# Trail__Con.net
KiCad netlist of a schematic drawn in EAGLE
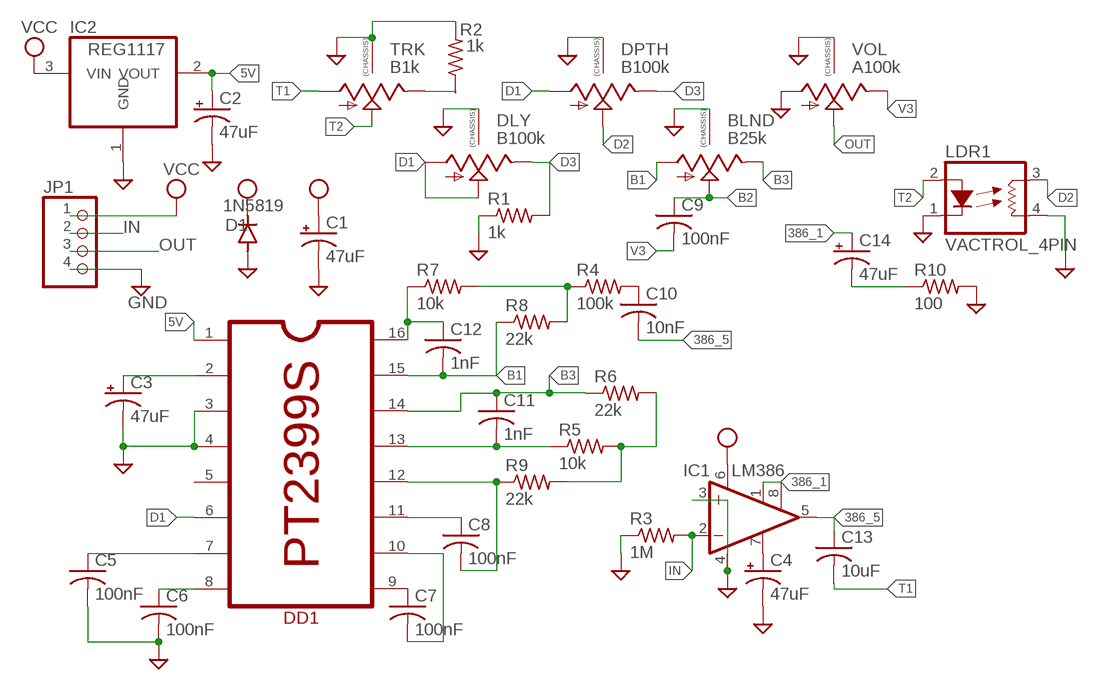
[diagram p0: schematic, sheet 1]

(export (version "E")
  (design (tool "Eeschema 10.0.6"))
  (components
    (comp (ref "BLND")
      (value "B25k")
      (footprint "eagle-import:9MM_SNAP-IN_POT")
      (libsource (lib "eagle-import") (part "9MM_SNAP-IN_POT_CHASSIS"))
    )
    (comp (ref "C1")
      (value "47uF")
      (footprint "eagle-import:PAN_B_SMD+THRU")
      (libsource (lib "eagle-import") (part "CAP_SMD+THRUPAN_B"))
    )
    (comp (ref "C2")
      (value "47uF")
      (footprint "eagle-import:PAN_B_SMD+THRU")
      (libsource (lib "eagle-import") (part "CAP_SMD+THRUPAN_B"))
    )
    (comp (ref "C3")
      (value "47uF")
      (footprint "eagle-import:PAN_B_SMD+THRU")
      (libsource (lib "eagle-import") (part "CAP_SMD+THRUPAN_B"))
    )
    (comp (ref "C4")
      (value "47uF")
      (footprint "eagle-import:PAN_B_SMD+THRU")
      (libsource (lib "eagle-import") (part "CAP_SMD+THRUPAN_B"))
    )
    (comp (ref "C5")
      (value "100nF")
      (footprint "eagle-import:C0402")
      (libsource (lib "eagle-import") (part "C-USC0402"))
    )
    (comp (ref "C6")
      (value "100nF")
      (footprint "eagle-import:C0402")
      (libsource (lib "eagle-import") (part "C-USC0402"))
    )
    (comp (ref "C7")
      (value "100nF")
      (footprint "eagle-import:C0402")
      (libsource (lib "eagle-import") (part "C-USC0402"))
    )
    (comp (ref "C8")
      (value "100nF")
      (footprint "eagle-import:C0402")
      (libsource (lib "eagle-import") (part "C-USC0402"))
    )
    (comp (ref "C9")
      (value "100nF")
      (footprint "eagle-import:C0402")
      (libsource (lib "eagle-import") (part "C-USC0402"))
    )
    (comp (ref "C10")
      (value "10nF")
      (footprint "eagle-import:C0402")
      (libsource (lib "eagle-import") (part "C-USC0402"))
    )
    (comp (ref "C11")
      (value "1nF")
      (footprint "eagle-import:C0402")
      (libsource (lib "eagle-import") (part "C-USC0402"))
    )
    (comp (ref "C12")
      (value "1nF")
      (footprint "eagle-import:C0402")
      (libsource (lib "eagle-import") (part "C-USC0402"))
    )
    (comp (ref "C13")
      (value "10uF")
      (footprint "eagle-import:C0805")
      (libsource (lib "eagle-import") (part "C-USC0805"))
    )
    (comp (ref "C14")
      (value "47uF")
      (footprint "eagle-import:PAN_B_SMD+THRU")
      (libsource (lib "eagle-import") (part "CAP_SMD+THRUPAN_B"))
    )
    (comp (ref "D1")
      (value "1N5819")
      (footprint "eagle-import:SOD123")
      (libsource (lib "eagle-import") (part "DIODE-SOD123"))
    )
    (comp (ref "DD1")
      (value "PT2399S")
      (footprint "eagle-import:SO-16")
      (libsource (lib "eagle-import") (part "PT2399S"))
    )
    (comp (ref "DLY")
      (value "B100k")
      (footprint "eagle-import:9MM_SNAP-IN_POT")
      (libsource (lib "eagle-import") (part "9MM_SNAP-IN_POT_CHASSIS"))
    )
    (comp (ref "DPTH")
      (value "B100k")
      (footprint "eagle-import:9MM_SNAP-IN_POT")
      (libsource (lib "eagle-import") (part "9MM_SNAP-IN_POT_CHASSIS"))
    )
    (comp (ref "IC1")
      (value "LM386")
      (footprint "eagle-import:SO08")
      (libsource (lib "eagle-import") (part "LM386?-M1"))
    )
    (comp (ref "IC2")
      (value "REG1117")
      (footprint "eagle-import:SOT223")
      (libsource (lib "eagle-import") (part "REG1117"))
    )
    (comp (ref "JP1")
      (value "PINHD-1X4")
      (footprint "eagle-import:1X04")
      (libsource (lib "eagle-import") (part "PINHD-1X4"))
    )
    (comp (ref "LDR1")
      (value "VACTROL_4PIN")
      (footprint "eagle-import:VACTROL_4PIN_VTL5C")
      (libsource (lib "eagle-import") (part "VACTROL_4PIN"))
    )
    (comp (ref "R1")
      (value "1k")
      (footprint "eagle-import:R0402")
      (libsource (lib "eagle-import") (part "R-US_R0402"))
    )
    (comp (ref "R2")
      (value "1k")
      (footprint "eagle-import:R0402")
      (libsource (lib "eagle-import") (part "R-US_R0402"))
    )
    (comp (ref "R3")
      (value "1M")
      (footprint "eagle-import:R0402")
      (libsource (lib "eagle-import") (part "R-US_R0402"))
    )
    (comp (ref "R4")
      (value "100k")
      (footprint "eagle-import:R0402")
      (libsource (lib "eagle-import") (part "R-US_R0402"))
    )
    (comp (ref "R5")
      (value "10k")
      (footprint "eagle-import:R0402")
      (libsource (lib "eagle-import") (part "R-US_R0402"))
    )
    (comp (ref "R6")
      (value "22k")
      (footprint "eagle-import:R0402")
      (libsource (lib "eagle-import") (part "R-US_R0402"))
    )
    (comp (ref "R7")
      (value "10k")
      (footprint "eagle-import:R0402")
      (libsource (lib "eagle-import") (part "R-US_R0402"))
    )
    (comp (ref "R8")
      (value "22k")
      (footprint "eagle-import:R0402")
      (libsource (lib "eagle-import") (part "R-US_R0402"))
    )
    (comp (ref "R9")
      (value "22k")
      (footprint "eagle-import:R0402")
      (libsource (lib "eagle-import") (part "R-US_R0402"))
    )
    (comp (ref "R10")
      (value "100")
      (footprint "eagle-import:R0402")
      (libsource (lib "eagle-import") (part "R-US_R0402"))
    )
    (comp (ref "TRK")
      (value "B1k")
      (footprint "eagle-import:9MM_SNAP-IN_POT")
      (libsource (lib "eagle-import") (part "9MM_SNAP-IN_POT_CHASSIS"))
    )
    (comp (ref "VOL")
      (value "A100k")
      (footprint "eagle-import:9MM_SNAP-IN_POT")
      (libsource (lib "eagle-import") (part "9MM_SNAP-IN_POT_CHASSIS"))
    )
  )
  (nets
    (net (code "1") (name "5V") (class "Default")
      (node (ref "C2") (pin "+") (pinfunction "+_+") (pintype "passive"))
      (node (ref "C2") (pin "++") (pinfunction "+_++") (pintype "passive"))
      (node (ref "DD1") (pin "1") (pinfunction "1_1") (pintype "bidirectional"))
      (node (ref "IC2") (pin "2") (pinfunction "VOUT_2") (pintype "output"))
    )
    (net (code "2") (name "386_1") (class "Default")
      (node (ref "C14") (pin "+") (pinfunction "+_+") (pintype "passive"))
      (node (ref "C14") (pin "++") (pinfunction "+_++") (pintype "passive"))
      (node (ref "IC1") (pin "1") (pinfunction "GAIN_1") (pintype "passive"))
      (node (ref "IC1") (pin "8") (pinfunction "GAIN_8") (pintype "passive"))
    )
    (net (code "3") (name "386_5") (class "Default")
      (node (ref "C10") (pin "2") (pinfunction "2_2") (pintype "passive"))
      (node (ref "C13") (pin "1") (pinfunction "1_1") (pintype "passive"))
      (node (ref "IC1") (pin "5") (pinfunction "OUT_5") (pintype "output"))
    )
    (net (code "4") (name "B1") (class "Default")
      (node (ref "BLND") (pin "1") (pinfunction "A_1") (pintype "passive"))
      (node (ref "C12") (pin "2") (pinfunction "2_2") (pintype "passive"))
      (node (ref "DD1") (pin "15") (pinfunction "15_15") (pintype "bidirectional"))
      (node (ref "R8") (pin "1") (pinfunction "1_1") (pintype "passive"))
    )
    (net (code "5") (name "B2") (class "Default")
      (node (ref "BLND") (pin "2") (pinfunction "S_2") (pintype "passive"))
      (node (ref "C9") (pin "1") (pinfunction "1_1") (pintype "passive"))
    )
    (net (code "6") (name "B3") (class "Default")
      (node (ref "BLND") (pin "3") (pinfunction "E_3") (pintype "passive"))
      (node (ref "C11") (pin "1") (pinfunction "1_1") (pintype "passive"))
      (node (ref "DD1") (pin "14") (pinfunction "14_14") (pintype "bidirectional"))
      (node (ref "R6") (pin "1") (pinfunction "1_1") (pintype "passive"))
    )
    (net (code "7") (name "D1") (class "Default")
      (node (ref "DD1") (pin "6") (pinfunction "6_6") (pintype "bidirectional"))
      (node (ref "DLY") (pin "1") (pinfunction "A_1") (pintype "passive"))
      (node (ref "DLY") (pin "2") (pinfunction "S_2") (pintype "passive"))
      (node (ref "DPTH") (pin "1") (pinfunction "A_1") (pintype "passive"))
    )
    (net (code "8") (name "D2") (class "Default")
      (node (ref "DPTH") (pin "2") (pinfunction "S_2") (pintype "passive"))
      (node (ref "LDR1") (pin "3") (pinfunction "RES1_3") (pintype "passive"))
    )
    (net (code "9") (name "D3") (class "Default")
      (node (ref "DLY") (pin "3") (pinfunction "E_3") (pintype "passive"))
      (node (ref "DPTH") (pin "3") (pinfunction "E_3") (pintype "passive"))
      (node (ref "R1") (pin "2") (pinfunction "2_2") (pintype "passive"))
    )
    (net (code "10") (name "GND") (class "Default")
      (node (ref "BLND") (pin "CHASSIS1") (pinfunction "P$1_CHASSIS1") (pintype "passive"))
      (node (ref "BLND") (pin "CHASSIS2") (pinfunction "P$1_CHASSIS2") (pintype "passive"))
      (node (ref "C1") (pin "-") (pinfunction "-_-") (pintype "passive"))
      (node (ref "C1") (pin "--") (pinfunction "-_--") (pintype "passive"))
      (node (ref "C2") (pin "-") (pinfunction "-_-") (pintype "passive"))
      (node (ref "C2") (pin "--") (pinfunction "-_--") (pintype "passive"))
      (node (ref "C3") (pin "-") (pinfunction "-_-") (pintype "passive"))
      (node (ref "C3") (pin "--") (pinfunction "-_--") (pintype "passive"))
      (node (ref "C4") (pin "-") (pinfunction "-_-") (pintype "passive"))
      (node (ref "C4") (pin "--") (pinfunction "-_--") (pintype "passive"))
      (node (ref "C5") (pin "2") (pinfunction "2_2") (pintype "passive"))
      (node (ref "C6") (pin "2") (pinfunction "2_2") (pintype "passive"))
      (node (ref "D1") (pin "A") (pinfunction "A_A") (pintype "passive"))
      (node (ref "DD1") (pin "3") (pinfunction "3_3") (pintype "bidirectional"))
      (node (ref "DD1") (pin "4") (pinfunction "4_4") (pintype "bidirectional"))
      (node (ref "DLY") (pin "CHASSIS1") (pinfunction "P$1_CHASSIS1") (pintype "passive"))
      (node (ref "DLY") (pin "CHASSIS2") (pinfunction "P$1_CHASSIS2") (pintype "passive"))
      (node (ref "DPTH") (pin "CHASSIS1") (pinfunction "P$1_CHASSIS1") (pintype "passive"))
      (node (ref "DPTH") (pin "CHASSIS2") (pinfunction "P$1_CHASSIS2") (pintype "passive"))
      (node (ref "IC1") (pin "3") (pinfunction "+IN_3") (pintype "input"))
      (node (ref "IC1") (pin "4") (pinfunction "GND_4") (pintype "power_in"))
      (node (ref "IC2") (pin "1") (pinfunction "GND_1") (pintype "power_in"))
      (node (ref "JP1") (pin "4") (pinfunction "4_4") (pintype "passive"))
      (node (ref "LDR1") (pin "1") (pinfunction "LED-_1") (pintype "passive"))
      (node (ref "LDR1") (pin "4") (pinfunction "RES2_4") (pintype "passive"))
      (node (ref "R1") (pin "1") (pinfunction "1_1") (pintype "passive"))
      (node (ref "R10") (pin "2") (pinfunction "2_2") (pintype "passive"))
      (node (ref "R2") (pin "2") (pinfunction "2_2") (pintype "passive"))
      (node (ref "R3") (pin "1") (pinfunction "1_1") (pintype "passive"))
      (node (ref "TRK") (pin "CHASSIS1") (pinfunction "P$1_CHASSIS1") (pintype "passive"))
      (node (ref "TRK") (pin "CHASSIS2") (pinfunction "P$1_CHASSIS2") (pintype "passive"))
      (node (ref "VOL") (pin "1") (pinfunction "A_1") (pintype "passive"))
      (node (ref "VOL") (pin "CHASSIS1") (pinfunction "P$1_CHASSIS1") (pintype "passive"))
      (node (ref "VOL") (pin "CHASSIS2") (pinfunction "P$1_CHASSIS2") (pintype "passive"))
    )
    (net (code "11") (name "IN") (class "Default")
      (node (ref "IC1") (pin "2") (pinfunction "-IN_2") (pintype "input"))
      (node (ref "JP1") (pin "2") (pinfunction "2_2") (pintype "passive"))
      (node (ref "R3") (pin "2") (pinfunction "2_2") (pintype "passive"))
    )
    (net (code "12") (name "Net-(C3-+-Pad++)") (class "Default")
      (node (ref "C3") (pin "+") (pinfunction "+_+") (pintype "passive"))
      (node (ref "C3") (pin "++") (pinfunction "+_++") (pintype "passive"))
      (node (ref "DD1") (pin "2") (pinfunction "2_2") (pintype "bidirectional"))
    )
    (net (code "13") (name "Net-(C5-Pad1)") (class "Default")
      (node (ref "C5") (pin "1") (pinfunction "1_1") (pintype "passive"))
      (node (ref "DD1") (pin "7") (pinfunction "7_7") (pintype "bidirectional"))
    )
    (net (code "14") (name "Net-(C6-Pad1)") (class "Default")
      (node (ref "C6") (pin "1") (pinfunction "1_1") (pintype "passive"))
      (node (ref "DD1") (pin "8") (pinfunction "8_8") (pintype "bidirectional"))
    )
    (net (code "15") (name "Net-(C7-Pad1)") (class "Default")
      (node (ref "C7") (pin "1") (pinfunction "1_1") (pintype "passive"))
      (node (ref "DD1") (pin "9") (pinfunction "9_9") (pintype "bidirectional"))
    )
    (net (code "16") (name "Net-(C7-Pad2)") (class "Default")
      (node (ref "C7") (pin "2") (pinfunction "2_2") (pintype "passive"))
      (node (ref "DD1") (pin "10") (pinfunction "10_10") (pintype "bidirectional"))
    )
    (net (code "17") (name "Net-(C8-Pad1)") (class "Default")
      (node (ref "C8") (pin "1") (pinfunction "1_1") (pintype "passive"))
      (node (ref "DD1") (pin "11") (pinfunction "11_11") (pintype "bidirectional"))
    )
    (net (code "18") (name "Net-(C8-Pad2)") (class "Default")
      (node (ref "C8") (pin "2") (pinfunction "2_2") (pintype "passive"))
      (node (ref "DD1") (pin "12") (pinfunction "12_12") (pintype "bidirectional"))
      (node (ref "R9") (pin "1") (pinfunction "1_1") (pintype "passive"))
    )
    (net (code "19") (name "Net-(C10-Pad1)") (class "Default")
      (node (ref "C10") (pin "1") (pinfunction "1_1") (pintype "passive"))
      (node (ref "R4") (pin "2") (pinfunction "2_2") (pintype "passive"))
    )
    (net (code "20") (name "Net-(C11-Pad2)") (class "Default")
      (node (ref "C11") (pin "2") (pinfunction "2_2") (pintype "passive"))
      (node (ref "DD1") (pin "13") (pinfunction "13_13") (pintype "bidirectional"))
      (node (ref "R5") (pin "1") (pinfunction "1_1") (pintype "passive"))
    )
    (net (code "21") (name "Net-(C12-Pad1)") (class "Default")
      (node (ref "C12") (pin "1") (pinfunction "1_1") (pintype "passive"))
      (node (ref "DD1") (pin "16") (pinfunction "16_16") (pintype "bidirectional"))
      (node (ref "R7") (pin "1") (pinfunction "1_1") (pintype "passive"))
    )
    (net (code "22") (name "Net-(C14---Pad--)") (class "Default")
      (node (ref "C14") (pin "-") (pinfunction "-_-") (pintype "passive"))
      (node (ref "C14") (pin "--") (pinfunction "-_--") (pintype "passive"))
      (node (ref "R10") (pin "1") (pinfunction "1_1") (pintype "passive"))
    )
    (net (code "23") (name "Net-(IC1-BYPASS)") (class "Default")
      (node (ref "C4") (pin "+") (pinfunction "+_+") (pintype "passive"))
      (node (ref "C4") (pin "++") (pinfunction "+_++") (pintype "passive"))
      (node (ref "IC1") (pin "7") (pinfunction "BYPASS_7") (pintype "passive"))
    )
    (net (code "24") (name "Net-(R4-Pad1)") (class "Default")
      (node (ref "R4") (pin "1") (pinfunction "1_1") (pintype "passive"))
      (node (ref "R7") (pin "2") (pinfunction "2_2") (pintype "passive"))
      (node (ref "R8") (pin "2") (pinfunction "2_2") (pintype "passive"))
    )
    (net (code "25") (name "Net-(R5-Pad2)") (class "Default")
      (node (ref "R5") (pin "2") (pinfunction "2_2") (pintype "passive"))
      (node (ref "R6") (pin "2") (pinfunction "2_2") (pintype "passive"))
      (node (ref "R9") (pin "2") (pinfunction "2_2") (pintype "passive"))
    )
    (net (code "26") (name "Net-(TRK-E)") (class "Default")
      (node (ref "R2") (pin "1") (pinfunction "1_1") (pintype "passive"))
      (node (ref "TRK") (pin "3") (pinfunction "E_3") (pintype "passive"))
    )
    (net (code "27") (name "OUT") (class "Default")
      (node (ref "JP1") (pin "3") (pinfunction "3_3") (pintype "passive"))
      (node (ref "VOL") (pin "2") (pinfunction "S_2") (pintype "passive"))
    )
    (net (code "28") (name "T1") (class "Default")
      (node (ref "C13") (pin "2") (pinfunction "2_2") (pintype "passive"))
      (node (ref "TRK") (pin "1") (pinfunction "A_1") (pintype "passive"))
    )
    (net (code "29") (name "T2") (class "Default")
      (node (ref "LDR1") (pin "2") (pinfunction "LED+_2") (pintype "passive"))
      (node (ref "TRK") (pin "2") (pinfunction "S_2") (pintype "passive"))
    )
    (net (code "30") (name "V3") (class "Default")
      (node (ref "C9") (pin "2") (pinfunction "2_2") (pintype "passive"))
      (node (ref "VOL") (pin "3") (pinfunction "E_3") (pintype "passive"))
    )
    (net (code "31") (name "VCC") (class "Default")
      (node (ref "C1") (pin "+") (pinfunction "+_+") (pintype "passive"))
      (node (ref "C1") (pin "++") (pinfunction "+_++") (pintype "passive"))
      (node (ref "D1") (pin "C") (pinfunction "C_C") (pintype "passive"))
      (node (ref "IC1") (pin "6") (pinfunction "VS_6") (pintype "power_in"))
      (node (ref "IC2") (pin "3") (pinfunction "VIN_3") (pintype "input"))
      (node (ref "JP1") (pin "1") (pinfunction "1_1") (pintype "passive"))
    )
    (net (code "32") (name "unconnected-(DD1-Pad5)") (class "Default")
      (node (ref "DD1") (pin "5") (pinfunction "5_5") (pintype "bidirectional"))
    )
  )
)
